# Recepitor.net
KiCad netlist of a schematic drawn in Altium Designer
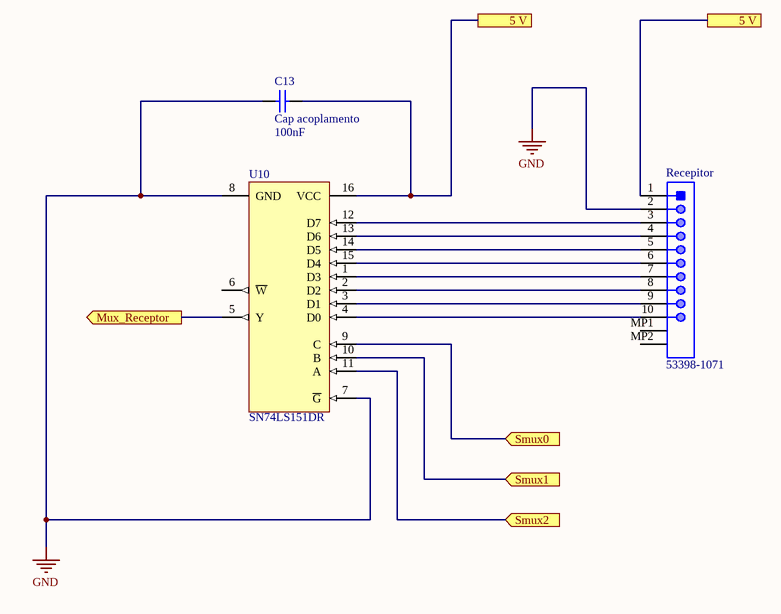
[diagram p0: Recepitor.SchDoc]

(export (version "E")
  (design (tool "Eeschema 10.0.6"))
  (components
    (comp (ref "C13")
      (value "Cap acoplamento")
      (footprint "C1206")
      (description "Capacitor (Semiconductor SIM Model)")
      (fields (field (name "ALTIUM_VALUE") "100nF") (field (name "PUBLISHER") "Altium Limited"))
      (libsource (lib "Miscellaneous Devices") (part "Cap Semi"))
    )
    (comp (ref "Recepitor")
      (value "53398-1071")
      (footprint "MOLX-53398-1071_V")
      (description "Male Header, Pitch 1.25 mm, 1 x 10 Position, Height 4.7 mm, -40 to 85 degC, RoHS, Tape and Reel")
      (fields (field (name "MANUFACTURER") "Molex"))
      (libsource (lib "Molex_53398-1071") (part "CMP-2000-05635-1"))
    )
    (comp (ref "U10")
      (value "SN74LS151DR")
      (footprint "D0016A_L")
      (description "8-Line To 1-Line Data Selectors/Multiplexers, D0016A, LARGE T&R")
      (fields
        (field (name "MANUFACTURER") "Texas Instruments")
        (field (name "GENERIC PART NUMBER") "SN74LS151")
      )
      (libsource (lib "mux SN74LS151DR") (part "CMP-1633-00148-1"))
    )
  )
  (nets
    (net (code "1") (name "/5 V") (class "Default")
      (node (ref "C13") (pin "2") (pinfunction "2_2") (pintype "passive"))
      (node (ref "Recepitor") (pin "1") (pinfunction "1_1") (pintype "passive"))
      (node (ref "U10") (pin "16") (pinfunction "VCC_16") (pintype "power_in"))
    )
    (net (code "2") (name "/Mux_Receptor") (class "Default")
      (node (ref "U10") (pin "5") (pinfunction "Y_5") (pintype "output"))
    )
    (net (code "3") (name "/Smux0") (class "Default")
      (node (ref "U10") (pin "9") (pinfunction "C_9") (pintype "input"))
    )
    (net (code "4") (name "/Smux1") (class "Default")
      (node (ref "U10") (pin "10") (pinfunction "B_10") (pintype "input"))
    )
    (net (code "5") (name "/Smux2") (class "Default")
      (node (ref "U10") (pin "11") (pinfunction "A_11") (pintype "input"))
    )
    (net (code "6") (name "GND") (class "Default")
      (node (ref "C13") (pin "1") (pinfunction "1_1") (pintype "passive"))
      (node (ref "Recepitor") (pin "2") (pinfunction "2_2") (pintype "passive"))
      (node (ref "U10") (pin "7") (pinfunction "~{G}_7") (pintype "input"))
      (node (ref "U10") (pin "8") (pinfunction "GND_8") (pintype "power_in"))
    )
    (net (code "7") (name "Net-(U10-D0)") (class "Default")
      (node (ref "Recepitor") (pin "10") (pinfunction "10_10") (pintype "passive"))
      (node (ref "U10") (pin "4") (pinfunction "D0_4") (pintype "input"))
    )
    (net (code "8") (name "Net-(U10-D1)") (class "Default")
      (node (ref "Recepitor") (pin "9") (pinfunction "9_9") (pintype "passive"))
      (node (ref "U10") (pin "3") (pinfunction "D1_3") (pintype "input"))
    )
    (net (code "9") (name "Net-(U10-D2)") (class "Default")
      (node (ref "Recepitor") (pin "8") (pinfunction "8_8") (pintype "passive"))
      (node (ref "U10") (pin "2") (pinfunction "D2_2") (pintype "input"))
    )
    (net (code "10") (name "Net-(U10-D3)") (class "Default")
      (node (ref "Recepitor") (pin "7") (pinfunction "7_7") (pintype "passive"))
      (node (ref "U10") (pin "1") (pinfunction "D3_1") (pintype "input"))
    )
    (net (code "11") (name "Net-(U10-D4)") (class "Default")
      (node (ref "Recepitor") (pin "6") (pinfunction "6_6") (pintype "passive"))
      (node (ref "U10") (pin "15") (pinfunction "D4_15") (pintype "input"))
    )
    (net (code "12") (name "Net-(U10-D5)") (class "Default")
      (node (ref "Recepitor") (pin "5") (pinfunction "5_5") (pintype "passive"))
      (node (ref "U10") (pin "14") (pinfunction "D5_14") (pintype "input"))
    )
    (net (code "13") (name "Net-(U10-D6)") (class "Default")
      (node (ref "Recepitor") (pin "4") (pinfunction "4_4") (pintype "passive"))
      (node (ref "U10") (pin "13") (pinfunction "D6_13") (pintype "input"))
    )
    (net (code "14") (name "Net-(U10-D7)") (class "Default")
      (node (ref "Recepitor") (pin "3") (pinfunction "3_3") (pintype "passive"))
      (node (ref "U10") (pin "12") (pinfunction "D7_12") (pintype "input"))
    )
    (net (code "15") (name "unconnected-(Recepitor-PadMP1)") (class "Default")
      (node (ref "Recepitor") (pin "MP1") (pinfunction "MP1_MP1") (pintype "passive"))
    )
    (net (code "16") (name "unconnected-(Recepitor-PadMP2)") (class "Default")
      (node (ref "Recepitor") (pin "MP2") (pinfunction "MP2_MP2") (pintype "passive"))
    )
    (net (code "17") (name "unconnected-(U10-~{W}-Pad6)") (class "Default")
      (node (ref "U10") (pin "6") (pinfunction "~{W}_6") (pintype "output"))
    )
  )
)
